# Sensor_Board_Try2.net
KiCad netlist of a schematic drawn in EAGLE
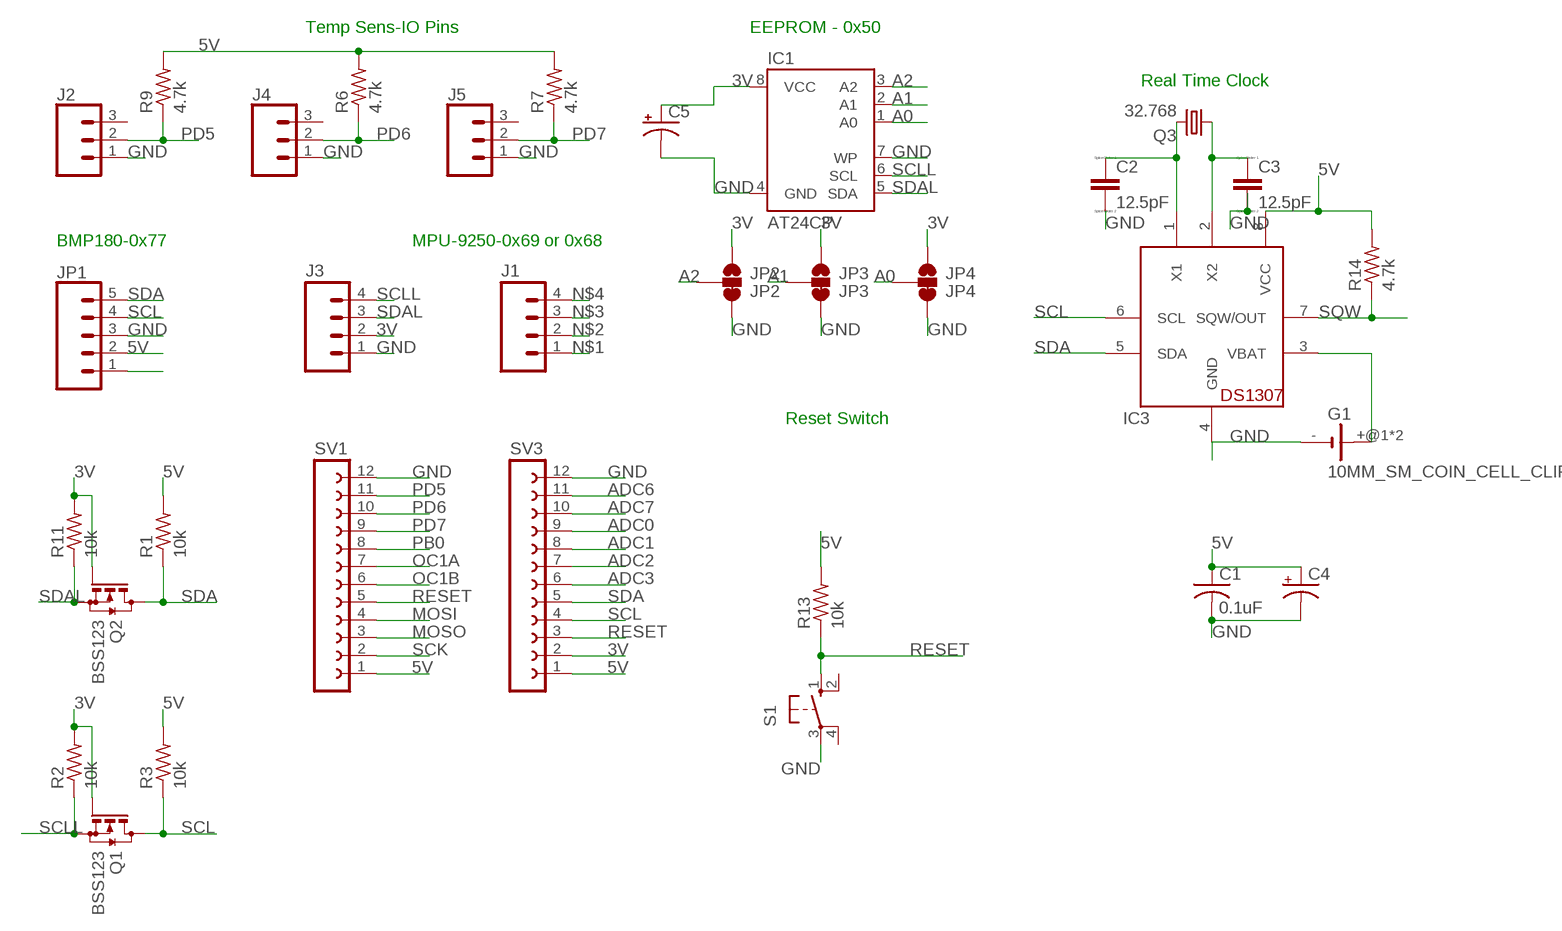
[diagram p0: schematic, sheet 1]

(export (version "E")
  (design (tool "Eeschema 10.0.6"))
  (components
    (comp (ref "C1")
      (value "0.1uF")
      (footprint "eagle-import:C025-025X050")
      (libsource (lib "eagle-import") (part "C-US025-025X050"))
    )
    (comp (ref "C2")
      (value "12.5pF")
      (footprint "eagle-import:C0805")
      (libsource (lib "eagle-import") (part "C"))
    )
    (comp (ref "C3")
      (value "12.5pF")
      (footprint "eagle-import:C0805")
      (libsource (lib "eagle-import") (part "C"))
    )
    (comp (ref "C4")
      (value "CPOL-USE2-4")
      (footprint "eagle-import:E2-4")
      (libsource (lib "eagle-import") (part "CPOL-USE2-4"))
    )
    (comp (ref "C5")
      (value "CPOL-USE2-4")
      (footprint "eagle-import:E2-4")
      (libsource (lib "eagle-import") (part "CPOL-USE2-4"))
    )
    (comp (ref "G1")
      (value "10MM_SM_COIN_CELL_CLIP")
      (footprint "eagle-import:10MM_SM_COIN_CELL_CLIP")
      (libsource (lib "eagle-import") (part "10MM_SM_COIN_CELL_CLIP"))
    )
    (comp (ref "IC1")
      (value "AT24CP")
      (footprint "eagle-import:DIL08")
      (fields (field (name "MPN") "AT24C1024BW-SH-B"))
      (libsource (lib "eagle-import") (part "AT24CP"))
    )
    (comp (ref "IC3")
      (value "DS1307")
      (footprint "eagle-import:DIL08")
      (libsource (lib "eagle-import") (part "DS1307"))
    )
    (comp (ref "J1")
      (value "M04PTH")
      (footprint "eagle-import:1X04")
      (libsource (lib "eagle-import") (part "M04PTH"))
    )
    (comp (ref "J2")
      (value "CONN_03")
      (footprint "eagle-import:1X03")
      (libsource (lib "eagle-import") (part "CONN_03"))
    )
    (comp (ref "J3")
      (value "M04PTH")
      (footprint "eagle-import:1X04")
      (libsource (lib "eagle-import") (part "M04PTH"))
    )
    (comp (ref "J4")
      (value "CONN_03")
      (footprint "eagle-import:1X03")
      (libsource (lib "eagle-import") (part "CONN_03"))
    )
    (comp (ref "J5")
      (value "CONN_03")
      (footprint "eagle-import:1X03")
      (libsource (lib "eagle-import") (part "CONN_03"))
    )
    (comp (ref "JP1")
      (value "CONN_05")
      (footprint "eagle-import:1X05")
      (libsource (lib "eagle-import") (part "CONN_05"))
    )
    (comp (ref "JP2")
      (value "JP2")
      (footprint "eagle-import:SMT-JUMPER_3_1-NC_TRACE_SILK")
      (libsource (lib "eagle-import") (part "JUMPER-SMT_3_1-NC_TRACE_SILK"))
    )
    (comp (ref "JP3")
      (value "JP3")
      (footprint "eagle-import:SMT-JUMPER_3_1-NC_TRACE_SILK")
      (libsource (lib "eagle-import") (part "JUMPER-SMT_3_1-NC_TRACE_SILK"))
    )
    (comp (ref "JP4")
      (value "JP4")
      (footprint "eagle-import:SMT-JUMPER_3_1-NC_TRACE_SILK")
      (libsource (lib "eagle-import") (part "JUMPER-SMT_3_1-NC_TRACE_SILK"))
    )
    (comp (ref "Q1")
      (value "BSS123")
      (footprint "eagle-import:SOT23")
      (libsource (lib "eagle-import") (part "BSS123"))
    )
    (comp (ref "Q2")
      (value "BSS123")
      (footprint "eagle-import:SOT23")
      (libsource (lib "eagle-import") (part "BSS123"))
    )
    (comp (ref "Q3")
      (value "32.768")
      (footprint "eagle-import:TC38H")
      (libsource (lib "eagle-import") (part "CRYTALTC38H"))
    )
    (comp (ref "R1")
      (value "10k")
      (footprint "eagle-import:M0805")
      (libsource (lib "eagle-import") (part "R-US_M0805"))
    )
    (comp (ref "R2")
      (value "10k")
      (footprint "eagle-import:M0805")
      (libsource (lib "eagle-import") (part "R-US_M0805"))
    )
    (comp (ref "R3")
      (value "10k")
      (footprint "eagle-import:M0805")
      (libsource (lib "eagle-import") (part "R-US_M0805"))
    )
    (comp (ref "R6")
      (value "4.7k")
      (footprint "eagle-import:M0805")
      (libsource (lib "eagle-import") (part "R-US_M0805"))
    )
    (comp (ref "R7")
      (value "4.7k")
      (footprint "eagle-import:M0805")
      (libsource (lib "eagle-import") (part "R-US_M0805"))
    )
    (comp (ref "R9")
      (value "4.7k")
      (footprint "eagle-import:M0805")
      (libsource (lib "eagle-import") (part "R-US_M0805"))
    )
    (comp (ref "R11")
      (value "10k")
      (footprint "eagle-import:M0805")
      (libsource (lib "eagle-import") (part "R-US_M0805"))
    )
    (comp (ref "R13")
      (value "10k")
      (footprint "eagle-import:M0805")
      (libsource (lib "eagle-import") (part "R-US_M0805"))
    )
    (comp (ref "R14")
      (value "4.7k")
      (footprint "eagle-import:M0805")
      (libsource (lib "eagle-import") (part "R-US_M0805"))
    )
    (comp (ref "S1")
      (value "10-XX")
      (footprint "eagle-import:B3F-10XX")
      (fields (field (name "MPN") "B3F-1000"))
      (libsource (lib "eagle-import") (part "10-XX"))
    )
    (comp (ref "SV1")
      (value "FE12-1")
      (footprint "eagle-import:FE12")
      (libsource (lib "eagle-import") (part "FE12-1"))
    )
    (comp (ref "SV3")
      (value "FE12-1")
      (footprint "eagle-import:FE12")
      (libsource (lib "eagle-import") (part "FE12-1"))
    )
  )
  (nets
    (net (code "1") (name "/3V") (class "Default")
      (node (ref "C5") (pin "+") (pinfunction "+_+") (pintype "passive"))
      (node (ref "IC1") (pin "8") (pinfunction "VCC_8") (pintype "power_in"))
      (node (ref "J3") (pin "2") (pinfunction "2_2") (pintype "passive"))
      (node (ref "JP2") (pin "1") (pinfunction "1_1") (pintype "passive"))
      (node (ref "JP3") (pin "1") (pinfunction "1_1") (pintype "passive"))
      (node (ref "JP4") (pin "1") (pinfunction "1_1") (pintype "passive"))
      (node (ref "Q1") (pin "1") (pinfunction "G_1") (pintype "passive"))
      (node (ref "Q2") (pin "1") (pinfunction "G_1") (pintype "passive"))
      (node (ref "R11") (pin "2") (pinfunction "2_2") (pintype "passive"))
      (node (ref "R2") (pin "2") (pinfunction "2_2") (pintype "passive"))
      (node (ref "SV3") (pin "2") (pinfunction "2_2") (pintype "passive"))
    )
    (net (code "2") (name "/5V") (class "Default")
      (node (ref "C1") (pin "1") (pinfunction "1_1") (pintype "passive"))
      (node (ref "C4") (pin "+") (pinfunction "+_+") (pintype "passive"))
      (node (ref "IC3") (pin "8") (pinfunction "VCC_8") (pintype "power_in"))
      (node (ref "JP1") (pin "2") (pinfunction "2_2") (pintype "passive"))
      (node (ref "R1") (pin "2") (pinfunction "2_2") (pintype "passive"))
      (node (ref "R13") (pin "2") (pinfunction "2_2") (pintype "passive"))
      (node (ref "R14") (pin "2") (pinfunction "2_2") (pintype "passive"))
      (node (ref "R3") (pin "2") (pinfunction "2_2") (pintype "passive"))
      (node (ref "R6") (pin "2") (pinfunction "2_2") (pintype "passive"))
      (node (ref "R7") (pin "2") (pinfunction "2_2") (pintype "passive"))
      (node (ref "R9") (pin "2") (pinfunction "2_2") (pintype "passive"))
      (node (ref "SV1") (pin "1") (pinfunction "1_1") (pintype "passive"))
      (node (ref "SV3") (pin "1") (pinfunction "1_1") (pintype "passive"))
    )
    (net (code "3") (name "/A0") (class "Default")
      (node (ref "IC1") (pin "1") (pinfunction "A0_1") (pintype "input"))
      (node (ref "JP4") (pin "2") (pinfunction "2_2") (pintype "passive"))
    )
    (net (code "4") (name "/A1") (class "Default")
      (node (ref "IC1") (pin "2") (pinfunction "A1_2") (pintype "input"))
      (node (ref "JP3") (pin "2") (pinfunction "2_2") (pintype "passive"))
    )
    (net (code "5") (name "/A2") (class "Default")
      (node (ref "IC1") (pin "3") (pinfunction "A2_3") (pintype "input"))
      (node (ref "JP2") (pin "2") (pinfunction "2_2") (pintype "passive"))
    )
    (net (code "6") (name "/ADC0") (class "Default")
      (node (ref "SV3") (pin "9") (pinfunction "9_9") (pintype "passive"))
    )
    (net (code "7") (name "/ADC1") (class "Default")
      (node (ref "SV3") (pin "8") (pinfunction "8_8") (pintype "passive"))
    )
    (net (code "8") (name "/ADC2") (class "Default")
      (node (ref "SV3") (pin "7") (pinfunction "7_7") (pintype "passive"))
    )
    (net (code "9") (name "/ADC3") (class "Default")
      (node (ref "SV3") (pin "6") (pinfunction "6_6") (pintype "passive"))
    )
    (net (code "10") (name "/ADC6") (class "Default")
      (node (ref "SV3") (pin "11") (pinfunction "11_11") (pintype "passive"))
    )
    (net (code "11") (name "/ADC7") (class "Default")
      (node (ref "SV3") (pin "10") (pinfunction "10_10") (pintype "passive"))
    )
    (net (code "12") (name "/GND") (class "Default")
      (node (ref "C1") (pin "2") (pinfunction "2_2") (pintype "passive"))
      (node (ref "C2") (pin "2") (pinfunction "2_2") (pintype "passive"))
      (node (ref "C3") (pin "2") (pinfunction "2_2") (pintype "passive"))
      (node (ref "C4") (pin "-") (pinfunction "-_-") (pintype "passive"))
      (node (ref "C5") (pin "-") (pinfunction "-_-") (pintype "passive"))
      (node (ref "G1") (pin "-") (pinfunction "-_-") (pintype "passive"))
      (node (ref "IC1") (pin "4") (pinfunction "GND_4") (pintype "power_in"))
      (node (ref "IC1") (pin "7") (pinfunction "WP_7") (pintype "input"))
      (node (ref "IC3") (pin "4") (pinfunction "GND_4") (pintype "power_in"))
      (node (ref "J2") (pin "1") (pinfunction "1_1") (pintype "passive"))
      (node (ref "J3") (pin "1") (pinfunction "1_1") (pintype "passive"))
      (node (ref "J4") (pin "1") (pinfunction "1_1") (pintype "passive"))
      (node (ref "J5") (pin "1") (pinfunction "1_1") (pintype "passive"))
      (node (ref "JP1") (pin "3") (pinfunction "3_3") (pintype "passive"))
      (node (ref "JP2") (pin "3") (pinfunction "3_3") (pintype "passive"))
      (node (ref "JP3") (pin "3") (pinfunction "3_3") (pintype "passive"))
      (node (ref "JP4") (pin "3") (pinfunction "3_3") (pintype "passive"))
      (node (ref "S1") (pin "3") (pinfunction "P_3") (pintype "passive"))
      (node (ref "SV1") (pin "12") (pinfunction "12_12") (pintype "passive"))
      (node (ref "SV3") (pin "12") (pinfunction "12_12") (pintype "passive"))
    )
    (net (code "13") (name "/MOSI") (class "Default")
      (node (ref "SV1") (pin "4") (pinfunction "4_4") (pintype "passive"))
    )
    (net (code "14") (name "/MOSO") (class "Default")
      (node (ref "SV1") (pin "3") (pinfunction "3_3") (pintype "passive"))
    )
    (net (code "15") (name "/N$1") (class "Default")
      (node (ref "J1") (pin "1") (pinfunction "1_1") (pintype "passive"))
    )
    (net (code "16") (name "/N$2") (class "Default")
      (node (ref "J1") (pin "2") (pinfunction "2_2") (pintype "passive"))
    )
    (net (code "17") (name "/N$3") (class "Default")
      (node (ref "J1") (pin "3") (pinfunction "3_3") (pintype "passive"))
    )
    (net (code "18") (name "/N$4") (class "Default")
      (node (ref "J1") (pin "4") (pinfunction "4_4") (pintype "passive"))
    )
    (net (code "19") (name "/OC1A") (class "Default")
      (node (ref "SV1") (pin "7") (pinfunction "7_7") (pintype "passive"))
    )
    (net (code "20") (name "/OC1B") (class "Default")
      (node (ref "SV1") (pin "6") (pinfunction "6_6") (pintype "passive"))
    )
    (net (code "21") (name "/PB0") (class "Default")
      (node (ref "SV1") (pin "8") (pinfunction "8_8") (pintype "passive"))
    )
    (net (code "22") (name "/PD5") (class "Default")
      (node (ref "J2") (pin "2") (pinfunction "2_2") (pintype "passive"))
      (node (ref "R9") (pin "1") (pinfunction "1_1") (pintype "passive"))
      (node (ref "SV1") (pin "11") (pinfunction "11_11") (pintype "passive"))
    )
    (net (code "23") (name "/PD6") (class "Default")
      (node (ref "J4") (pin "2") (pinfunction "2_2") (pintype "passive"))
      (node (ref "R6") (pin "1") (pinfunction "1_1") (pintype "passive"))
      (node (ref "SV1") (pin "10") (pinfunction "10_10") (pintype "passive"))
    )
    (net (code "24") (name "/PD7") (class "Default")
      (node (ref "J5") (pin "2") (pinfunction "2_2") (pintype "passive"))
      (node (ref "R7") (pin "1") (pinfunction "1_1") (pintype "passive"))
      (node (ref "SV1") (pin "9") (pinfunction "9_9") (pintype "passive"))
    )
    (net (code "25") (name "/RESET") (class "Default")
      (node (ref "R13") (pin "1") (pinfunction "1_1") (pintype "passive"))
      (node (ref "S1") (pin "1") (pinfunction "S_1") (pintype "passive"))
      (node (ref "SV1") (pin "5") (pinfunction "5_5") (pintype "passive"))
      (node (ref "SV3") (pin "3") (pinfunction "3_3") (pintype "passive"))
    )
    (net (code "26") (name "/SCK") (class "Default")
      (node (ref "SV1") (pin "2") (pinfunction "2_2") (pintype "passive"))
    )
    (net (code "27") (name "/SCL") (class "Default")
      (node (ref "IC3") (pin "6") (pinfunction "SCL_6") (pintype "bidirectional"))
      (node (ref "JP1") (pin "4") (pinfunction "4_4") (pintype "passive"))
      (node (ref "Q1") (pin "3") (pinfunction "D_3") (pintype "passive"))
      (node (ref "R3") (pin "1") (pinfunction "1_1") (pintype "passive"))
      (node (ref "SV3") (pin "4") (pinfunction "4_4") (pintype "passive"))
    )
    (net (code "28") (name "/SCLL") (class "Default")
      (node (ref "IC1") (pin "6") (pinfunction "SCL_6") (pintype "bidirectional"))
      (node (ref "J3") (pin "4") (pinfunction "4_4") (pintype "passive"))
      (node (ref "Q1") (pin "2") (pinfunction "S_2") (pintype "passive"))
      (node (ref "R2") (pin "1") (pinfunction "1_1") (pintype "passive"))
    )
    (net (code "29") (name "/SDA") (class "Default")
      (node (ref "IC3") (pin "5") (pinfunction "SDA_5") (pintype "bidirectional"))
      (node (ref "JP1") (pin "5") (pinfunction "5_5") (pintype "passive"))
      (node (ref "Q2") (pin "3") (pinfunction "D_3") (pintype "passive"))
      (node (ref "R1") (pin "1") (pinfunction "1_1") (pintype "passive"))
      (node (ref "SV3") (pin "5") (pinfunction "5_5") (pintype "passive"))
    )
    (net (code "30") (name "/SDAL") (class "Default")
      (node (ref "IC1") (pin "5") (pinfunction "SDA_5") (pintype "bidirectional"))
      (node (ref "J3") (pin "3") (pinfunction "3_3") (pintype "passive"))
      (node (ref "Q2") (pin "2") (pinfunction "S_2") (pintype "passive"))
      (node (ref "R11") (pin "1") (pinfunction "1_1") (pintype "passive"))
    )
    (net (code "31") (name "/SQW") (class "Default")
      (node (ref "IC3") (pin "7") (pinfunction "SQW/OUT_7") (pintype "bidirectional"))
      (node (ref "R14") (pin "1") (pinfunction "1_1") (pintype "passive"))
    )
    (net (code "32") (name "Net-(IC3-VBAT)") (class "Default")
      (node (ref "G1") (pin "+@1") (pinfunction "+_+@1") (pintype "passive"))
      (node (ref "G1") (pin "+@2") (pinfunction "+_+@2") (pintype "passive"))
      (node (ref "IC3") (pin "3") (pinfunction "VBAT_3") (pintype "power_in"))
    )
    (net (code "33") (name "Net-(IC3-X1)") (class "Default")
      (node (ref "C2") (pin "1") (pinfunction "1_1") (pintype "passive"))
      (node (ref "IC3") (pin "1") (pinfunction "X1_1") (pintype "passive"))
      (node (ref "Q3") (pin "2") (pinfunction "2_2") (pintype "passive"))
    )
    (net (code "34") (name "Net-(IC3-X2)") (class "Default")
      (node (ref "C3") (pin "1") (pinfunction "1_1") (pintype "passive"))
      (node (ref "IC3") (pin "2") (pinfunction "X2_2") (pintype "passive"))
      (node (ref "Q3") (pin "1") (pinfunction "1_1") (pintype "passive"))
    )
    (net (code "35") (name "unconnected-(J2-Pad3)") (class "Default")
      (node (ref "J2") (pin "3") (pinfunction "3_3") (pintype "passive"))
    )
    (net (code "36") (name "unconnected-(J4-Pad3)") (class "Default")
      (node (ref "J4") (pin "3") (pinfunction "3_3") (pintype "passive"))
    )
    (net (code "37") (name "unconnected-(J5-Pad3)") (class "Default")
      (node (ref "J5") (pin "3") (pinfunction "3_3") (pintype "passive"))
    )
    (net (code "38") (name "unconnected-(JP1-Pad1)") (class "Default")
      (node (ref "JP1") (pin "1") (pinfunction "1_1") (pintype "passive"))
    )
    (net (code "39") (name "unconnected-(S1-P1-Pad4)") (class "Default")
      (node (ref "S1") (pin "4") (pinfunction "P1_4") (pintype "passive"))
    )
    (net (code "40") (name "unconnected-(S1-S1-Pad2)") (class "Default")
      (node (ref "S1") (pin "2") (pinfunction "S1_2") (pintype "passive"))
    )
  )
)
